# mcuWallPower.net
KiCad netlist of a schematic drawn in EAGLE
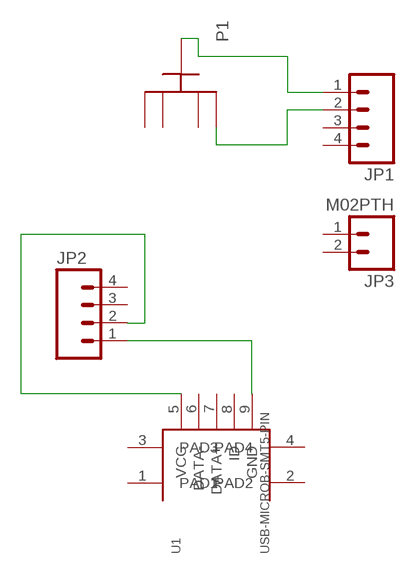
[diagram p0: schematic, sheet 1]

(export (version "E")
  (design (tool "Eeschema 10.0.6"))
  (components
    (comp (ref "JP1")
      (value "M04PTH")
      (footprint "eagle-import:1X04")
      (libsource (lib "eagle-import") (part "M04PTH"))
    )
    (comp (ref "JP2")
      (value "M04PTH")
      (footprint "eagle-import:1X04")
      (libsource (lib "eagle-import") (part "M04PTH"))
    )
    (comp (ref "JP3")
      (value "M02PTH")
      (footprint "eagle-import:1X02")
      (libsource (lib "eagle-import") (part "M02PTH"))
    )
    (comp (ref "P1")
      (value "CR2032")
      (footprint "eagle-import:CR2032_2025")
      (libsource (lib "eagle-import") (part "CR2032"))
    )
    (comp (ref "U1")
      (value "USB-MICROB-SMT5-PIN")
      (footprint "eagle-import:USB-MICROB-SMT")
      (libsource (lib "eagle-import") (part "USB-MICROB-SMT5-PIN"))
    )
  )
  (nets
    (net (code "1") (name "Net-(JP1-Pad1)") (class "Default")
      (node (ref "JP1") (pin "1") (pinfunction "1_1") (pintype "passive"))
      (node (ref "P1") (pin "GND") (pinfunction "GND_GND") (pintype "bidirectional"))
    )
    (net (code "2") (name "Net-(JP1-Pad2)") (class "Default")
      (node (ref "JP1") (pin "2") (pinfunction "2_2") (pintype "passive"))
      (node (ref "P1") (pin "VCC_1") (pinfunction "VCC_1_VCC_1") (pintype "bidirectional"))
    )
    (net (code "3") (name "Net-(U1-GND)") (class "Default")
      (node (ref "JP2") (pin "1") (pinfunction "1_1") (pintype "passive"))
      (node (ref "U1") (pin "9") (pinfunction "GND_9") (pintype "bidirectional"))
    )
    (net (code "4") (name "Net-(U1-VCC)") (class "Default")
      (node (ref "JP2") (pin "2") (pinfunction "2_2") (pintype "passive"))
      (node (ref "U1") (pin "5") (pinfunction "VCC_5") (pintype "bidirectional"))
    )
    (net (code "5") (name "unconnected-(JP1-Pad3)") (class "Default")
      (node (ref "JP1") (pin "3") (pinfunction "3_3") (pintype "passive"))
    )
    (net (code "6") (name "unconnected-(JP1-Pad4)") (class "Default")
      (node (ref "JP1") (pin "4") (pinfunction "4_4") (pintype "passive"))
    )
    (net (code "7") (name "unconnected-(JP2-Pad3)") (class "Default")
      (node (ref "JP2") (pin "3") (pinfunction "3_3") (pintype "passive"))
    )
    (net (code "8") (name "unconnected-(JP2-Pad4)") (class "Default")
      (node (ref "JP2") (pin "4") (pinfunction "4_4") (pintype "passive"))
    )
    (net (code "9") (name "unconnected-(JP3-Pad1)") (class "Default")
      (node (ref "JP3") (pin "1") (pinfunction "1_1") (pintype "passive"))
    )
    (net (code "10") (name "unconnected-(JP3-Pad2)") (class "Default")
      (node (ref "JP3") (pin "2") (pinfunction "2_2") (pintype "passive"))
    )
    (net (code "11") (name "unconnected-(P1-PadVCC_2)") (class "Default")
      (node (ref "P1") (pin "VCC_2") (pinfunction "VCC_2_VCC_2") (pintype "bidirectional"))
    )
    (net (code "12") (name "unconnected-(P1-PadVCC_3)") (class "Default")
      (node (ref "P1") (pin "VCC_3") (pinfunction "VCC_3_VCC_3") (pintype "bidirectional"))
    )
    (net (code "13") (name "unconnected-(P1-PadVCC_4)") (class "Default")
      (node (ref "P1") (pin "VCC_4") (pinfunction "VCC_4_VCC_4") (pintype "bidirectional"))
    )
    (net (code "14") (name "unconnected-(U1-DATA+-Pad7)") (class "Default")
      (node (ref "U1") (pin "7") (pinfunction "DATA+_7") (pintype "bidirectional"))
    )
    (net (code "15") (name "unconnected-(U1-DATA--Pad6)") (class "Default")
      (node (ref "U1") (pin "6") (pinfunction "DATA-_6") (pintype "bidirectional"))
    )
    (net (code "16") (name "unconnected-(U1-ID-Pad8)") (class "Default")
      (node (ref "U1") (pin "8") (pinfunction "ID_8") (pintype "bidirectional"))
    )
    (net (code "17") (name "unconnected-(U1-PAD1-Pad1)") (class "Default")
      (node (ref "U1") (pin "1") (pinfunction "PAD1_1") (pintype "no_connect"))
    )
    (net (code "18") (name "unconnected-(U1-PAD2-Pad2)") (class "Default")
      (node (ref "U1") (pin "2") (pinfunction "PAD2_2") (pintype "no_connect"))
    )
    (net (code "19") (name "unconnected-(U1-PAD3-Pad3)") (class "Default")
      (node (ref "U1") (pin "3") (pinfunction "PAD3_3") (pintype "no_connect"))
    )
    (net (code "20") (name "unconnected-(U1-PAD4-Pad4)") (class "Default")
      (node (ref "U1") (pin "4") (pinfunction "PAD4_4") (pintype "no_connect"))
    )
  )
)
